# counter.net
KiCad netlist of a schematic drawn in EAGLE
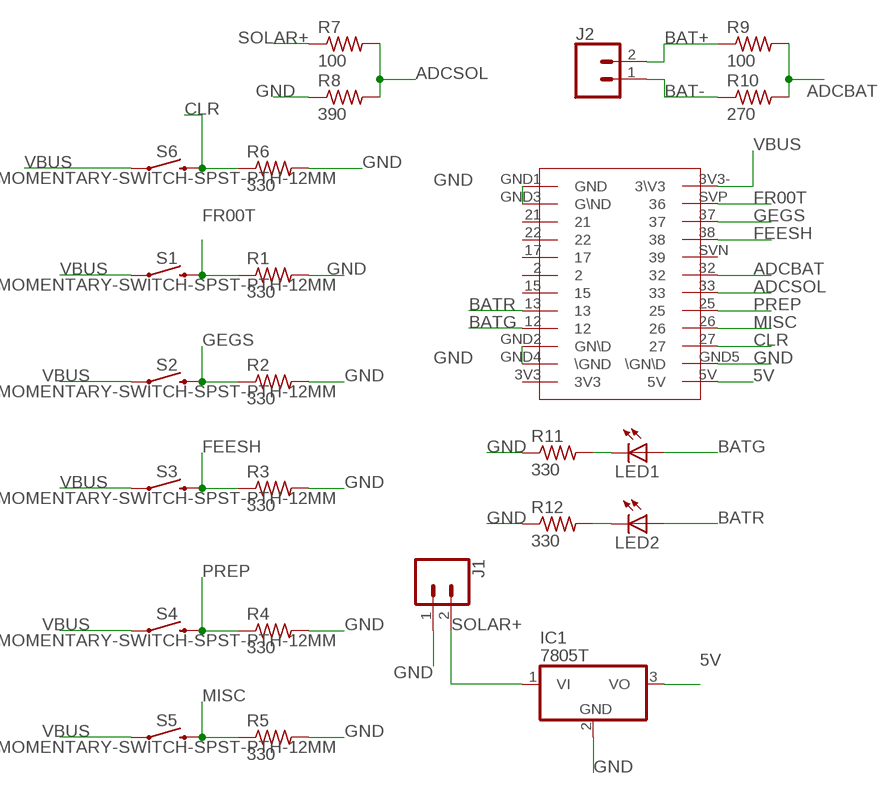
[diagram p0: schematic, sheet 1]

(export (version "E")
  (design (tool "Eeschema 10.0.6"))
  (components
    (comp (ref "IC1")
      (value "7805T")
      (footprint "eagle-import:TO220H")
      (libsource (lib "eagle-import") (part "78T05"))
    )
    (comp (ref "J1")
      (value "CONN_02")
      (footprint "eagle-import:1X02")
      (libsource (lib "eagle-import") (part "CONN_02"))
    )
    (comp (ref "J2")
      (value "CONN_02")
      (footprint "eagle-import:1X02")
      (libsource (lib "eagle-import") (part "CONN_02"))
    )
    (comp (ref "LED1")
      (value "LED3MM")
      (footprint "eagle-import:LED3MM")
      (libsource (lib "eagle-import") (part "LED3MM"))
    )
    (comp (ref "LED2")
      (value "LED3MM")
      (footprint "eagle-import:LED3MM")
      (libsource (lib "eagle-import") (part "LED3MM"))
    )
    (comp (ref "R1")
      (value "330")
      (footprint "eagle-import:0204_7")
      (libsource (lib "eagle-import") (part "R-US_0204/7"))
    )
    (comp (ref "R2")
      (value "330")
      (footprint "eagle-import:0204_7")
      (libsource (lib "eagle-import") (part "R-US_0204/7"))
    )
    (comp (ref "R3")
      (value "330")
      (footprint "eagle-import:0204_7")
      (libsource (lib "eagle-import") (part "R-US_0204/7"))
    )
    (comp (ref "R4")
      (value "330")
      (footprint "eagle-import:0204_7")
      (libsource (lib "eagle-import") (part "R-US_0204/7"))
    )
    (comp (ref "R5")
      (value "330")
      (footprint "eagle-import:0204_7")
      (libsource (lib "eagle-import") (part "R-US_0204/7"))
    )
    (comp (ref "R6")
      (value "330")
      (footprint "eagle-import:0204_7")
      (libsource (lib "eagle-import") (part "R-US_0204/7"))
    )
    (comp (ref "R7")
      (value "100")
      (footprint "eagle-import:0204_7")
      (libsource (lib "eagle-import") (part "R-US_0204/7"))
    )
    (comp (ref "R8")
      (value "390")
      (footprint "eagle-import:0204_7")
      (libsource (lib "eagle-import") (part "R-US_0204/7"))
    )
    (comp (ref "R9")
      (value "100")
      (footprint "eagle-import:0204_7")
      (libsource (lib "eagle-import") (part "R-US_0204/7"))
    )
    (comp (ref "R10")
      (value "270")
      (footprint "eagle-import:0204_7")
      (libsource (lib "eagle-import") (part "R-US_0204/7"))
    )
    (comp (ref "R11")
      (value "330")
      (footprint "eagle-import:0204_7")
      (libsource (lib "eagle-import") (part "R-US_0204/7"))
    )
    (comp (ref "R12")
      (value "330")
      (footprint "eagle-import:0204_7")
      (libsource (lib "eagle-import") (part "R-US_0204/7"))
    )
    (comp (ref "S1")
      (value "MOMENTARY-SWITCH-SPST-PTH-12MM")
      (footprint "eagle-import:TACTILE_SWITCH_PTH_12MM")
      (libsource (lib "eagle-import") (part "MOMENTARY-SWITCH-SPST-PTH-12MM"))
    )
    (comp (ref "S2")
      (value "MOMENTARY-SWITCH-SPST-PTH-12MM")
      (footprint "eagle-import:TACTILE_SWITCH_PTH_12MM")
      (libsource (lib "eagle-import") (part "MOMENTARY-SWITCH-SPST-PTH-12MM"))
    )
    (comp (ref "S3")
      (value "MOMENTARY-SWITCH-SPST-PTH-12MM")
      (footprint "eagle-import:TACTILE_SWITCH_PTH_12MM")
      (libsource (lib "eagle-import") (part "MOMENTARY-SWITCH-SPST-PTH-12MM"))
    )
    (comp (ref "S4")
      (value "MOMENTARY-SWITCH-SPST-PTH-12MM")
      (footprint "eagle-import:TACTILE_SWITCH_PTH_12MM")
      (libsource (lib "eagle-import") (part "MOMENTARY-SWITCH-SPST-PTH-12MM"))
    )
    (comp (ref "S5")
      (value "MOMENTARY-SWITCH-SPST-PTH-12MM")
      (footprint "eagle-import:TACTILE_SWITCH_PTH_12MM")
      (libsource (lib "eagle-import") (part "MOMENTARY-SWITCH-SPST-PTH-12MM"))
    )
    (comp (ref "S6")
      (value "MOMENTARY-SWITCH-SPST-PTH-12MM")
      (footprint "eagle-import:TACTILE_SWITCH_PTH_12MM")
      (libsource (lib "eagle-import") (part "MOMENTARY-SWITCH-SPST-PTH-12MM"))
    )
    (comp (ref "U$1")
      (value "TTGO-4MB")
      (footprint "eagle-import:ESP32-TTGO-TDISPLAY")
      (libsource (lib "eagle-import") (part "TTGO-4MB"))
    )
  )
  (nets
    (net (code "1") (name "/5V") (class "Default")
      (node (ref "IC1") (pin "3") (pinfunction "VO_3") (pintype "passive"))
      (node (ref "U$1") (pin "5V") (pinfunction "5V_5V") (pintype "bidirectional"))
    )
    (net (code "2") (name "/ADCBAT") (class "Default")
      (node (ref "R10") (pin "2") (pinfunction "2_2") (pintype "passive"))
      (node (ref "R9") (pin "2") (pinfunction "2_2") (pintype "passive"))
      (node (ref "U$1") (pin "32") (pinfunction "32_32") (pintype "bidirectional"))
    )
    (net (code "3") (name "/ADCSOL") (class "Default")
      (node (ref "R7") (pin "2") (pinfunction "2_2") (pintype "passive"))
      (node (ref "R8") (pin "2") (pinfunction "2_2") (pintype "passive"))
      (node (ref "U$1") (pin "33") (pinfunction "33_33") (pintype "bidirectional"))
    )
    (net (code "4") (name "/BAT+") (class "Default")
      (node (ref "J2") (pin "2") (pinfunction "2_2") (pintype "passive"))
      (node (ref "R9") (pin "1") (pinfunction "1_1") (pintype "passive"))
    )
    (net (code "5") (name "/BAT-") (class "Default")
      (node (ref "J2") (pin "1") (pinfunction "1_1") (pintype "passive"))
      (node (ref "R10") (pin "1") (pinfunction "1_1") (pintype "passive"))
    )
    (net (code "6") (name "/BATG") (class "Default")
      (node (ref "LED1") (pin "A") (pinfunction "A_A") (pintype "passive"))
      (node (ref "U$1") (pin "12") (pinfunction "12_12") (pintype "bidirectional"))
    )
    (net (code "7") (name "/BATR") (class "Default")
      (node (ref "LED2") (pin "A") (pinfunction "A_A") (pintype "passive"))
      (node (ref "U$1") (pin "13") (pinfunction "13_13") (pintype "bidirectional"))
    )
    (net (code "8") (name "/CLR") (class "Default")
      (node (ref "R6") (pin "1") (pinfunction "1_1") (pintype "passive"))
      (node (ref "S6") (pin "3") (pinfunction "2_3") (pintype "passive"))
      (node (ref "U$1") (pin "27") (pinfunction "27_27") (pintype "bidirectional"))
    )
    (net (code "9") (name "/FEESH") (class "Default")
      (node (ref "R3") (pin "1") (pinfunction "1_1") (pintype "passive"))
      (node (ref "S3") (pin "3") (pinfunction "2_3") (pintype "passive"))
      (node (ref "U$1") (pin "38") (pinfunction "38_38") (pintype "bidirectional"))
    )
    (net (code "10") (name "/FR00T") (class "Default")
      (node (ref "R1") (pin "1") (pinfunction "1_1") (pintype "passive"))
      (node (ref "S1") (pin "3") (pinfunction "2_3") (pintype "passive"))
      (node (ref "U$1") (pin "SVP") (pinfunction "36_SVP") (pintype "bidirectional"))
    )
    (net (code "11") (name "/GEGS") (class "Default")
      (node (ref "R2") (pin "1") (pinfunction "1_1") (pintype "passive"))
      (node (ref "S2") (pin "3") (pinfunction "2_3") (pintype "passive"))
      (node (ref "U$1") (pin "37") (pinfunction "37_37") (pintype "bidirectional"))
    )
    (net (code "12") (name "/GND") (class "Default")
      (node (ref "IC1") (pin "2") (pinfunction "GND_2") (pintype "passive"))
      (node (ref "J1") (pin "1") (pinfunction "1_1") (pintype "passive"))
      (node (ref "R1") (pin "2") (pinfunction "2_2") (pintype "passive"))
      (node (ref "R11") (pin "1") (pinfunction "1_1") (pintype "passive"))
      (node (ref "R12") (pin "1") (pinfunction "1_1") (pintype "passive"))
      (node (ref "R2") (pin "2") (pinfunction "2_2") (pintype "passive"))
      (node (ref "R3") (pin "2") (pinfunction "2_2") (pintype "passive"))
      (node (ref "R4") (pin "2") (pinfunction "2_2") (pintype "passive"))
      (node (ref "R5") (pin "2") (pinfunction "2_2") (pintype "passive"))
      (node (ref "R6") (pin "2") (pinfunction "2_2") (pintype "passive"))
      (node (ref "R8") (pin "1") (pinfunction "1_1") (pintype "passive"))
      (node (ref "U$1") (pin "GND1") (pinfunction "GND_GND1") (pintype "bidirectional"))
      (node (ref "U$1") (pin "GND2") (pinfunction "GN\\D_GND2") (pintype "bidirectional"))
      (node (ref "U$1") (pin "GND3") (pinfunction "G\\ND_GND3") (pintype "bidirectional"))
      (node (ref "U$1") (pin "GND4") (pinfunction "\\GND_GND4") (pintype "bidirectional"))
      (node (ref "U$1") (pin "GND5") (pinfunction "\\GN\\D_GND5") (pintype "bidirectional"))
    )
    (net (code "13") (name "/MISC") (class "Default")
      (node (ref "R5") (pin "1") (pinfunction "1_1") (pintype "passive"))
      (node (ref "S5") (pin "3") (pinfunction "2_3") (pintype "passive"))
      (node (ref "U$1") (pin "26") (pinfunction "26_26") (pintype "bidirectional"))
    )
    (net (code "14") (name "/PREP") (class "Default")
      (node (ref "R4") (pin "1") (pinfunction "1_1") (pintype "passive"))
      (node (ref "S4") (pin "3") (pinfunction "2_3") (pintype "passive"))
      (node (ref "U$1") (pin "25") (pinfunction "25_25") (pintype "bidirectional"))
    )
    (net (code "15") (name "/SOLAR+") (class "Default")
      (node (ref "IC1") (pin "1") (pinfunction "VI_1") (pintype "input"))
      (node (ref "J1") (pin "2") (pinfunction "2_2") (pintype "passive"))
      (node (ref "R7") (pin "1") (pinfunction "1_1") (pintype "passive"))
    )
    (net (code "16") (name "/VBUS") (class "Default")
      (node (ref "S1") (pin "1") (pinfunction "1_1") (pintype "passive"))
      (node (ref "S2") (pin "1") (pinfunction "1_1") (pintype "passive"))
      (node (ref "S3") (pin "1") (pinfunction "1_1") (pintype "passive"))
      (node (ref "S4") (pin "1") (pinfunction "1_1") (pintype "passive"))
      (node (ref "S5") (pin "1") (pinfunction "1_1") (pintype "passive"))
      (node (ref "S6") (pin "1") (pinfunction "1_1") (pintype "passive"))
      (node (ref "U$1") (pin "3V3-") (pinfunction "3\\V3_3V3-") (pintype "bidirectional"))
    )
    (net (code "17") (name "Net-(LED1-C)") (class "Default")
      (node (ref "LED1") (pin "K") (pinfunction "C_K") (pintype "passive"))
      (node (ref "R11") (pin "2") (pinfunction "2_2") (pintype "passive"))
    )
    (net (code "18") (name "Net-(LED2-C)") (class "Default")
      (node (ref "LED2") (pin "K") (pinfunction "C_K") (pintype "passive"))
      (node (ref "R12") (pin "2") (pinfunction "2_2") (pintype "passive"))
    )
    (net (code "19") (name "unconnected-(U$1-39-PadSVN)") (class "Default")
      (node (ref "U$1") (pin "SVN") (pinfunction "39_SVN") (pintype "bidirectional"))
    )
    (net (code "20") (name "unconnected-(U$1-Pad2)") (class "Default")
      (node (ref "U$1") (pin "2") (pinfunction "2_2") (pintype "bidirectional"))
    )
    (net (code "21") (name "unconnected-(U$1-Pad3V3)") (class "Default")
      (node (ref "U$1") (pin "3V3") (pinfunction "3V3_3V3") (pintype "bidirectional"))
    )
    (net (code "22") (name "unconnected-(U$1-Pad15)") (class "Default")
      (node (ref "U$1") (pin "15") (pinfunction "15_15") (pintype "bidirectional"))
    )
    (net (code "23") (name "unconnected-(U$1-Pad17)") (class "Default")
      (node (ref "U$1") (pin "17") (pinfunction "17_17") (pintype "bidirectional"))
    )
    (net (code "24") (name "unconnected-(U$1-Pad21)") (class "Default")
      (node (ref "U$1") (pin "21") (pinfunction "21_21") (pintype "bidirectional"))
    )
    (net (code "25") (name "unconnected-(U$1-Pad22)") (class "Default")
      (node (ref "U$1") (pin "22") (pinfunction "22_22") (pintype "bidirectional"))
    )
  )
)
